# CircuitDesign.net
KiCad netlist of a schematic drawn in Altium Designer
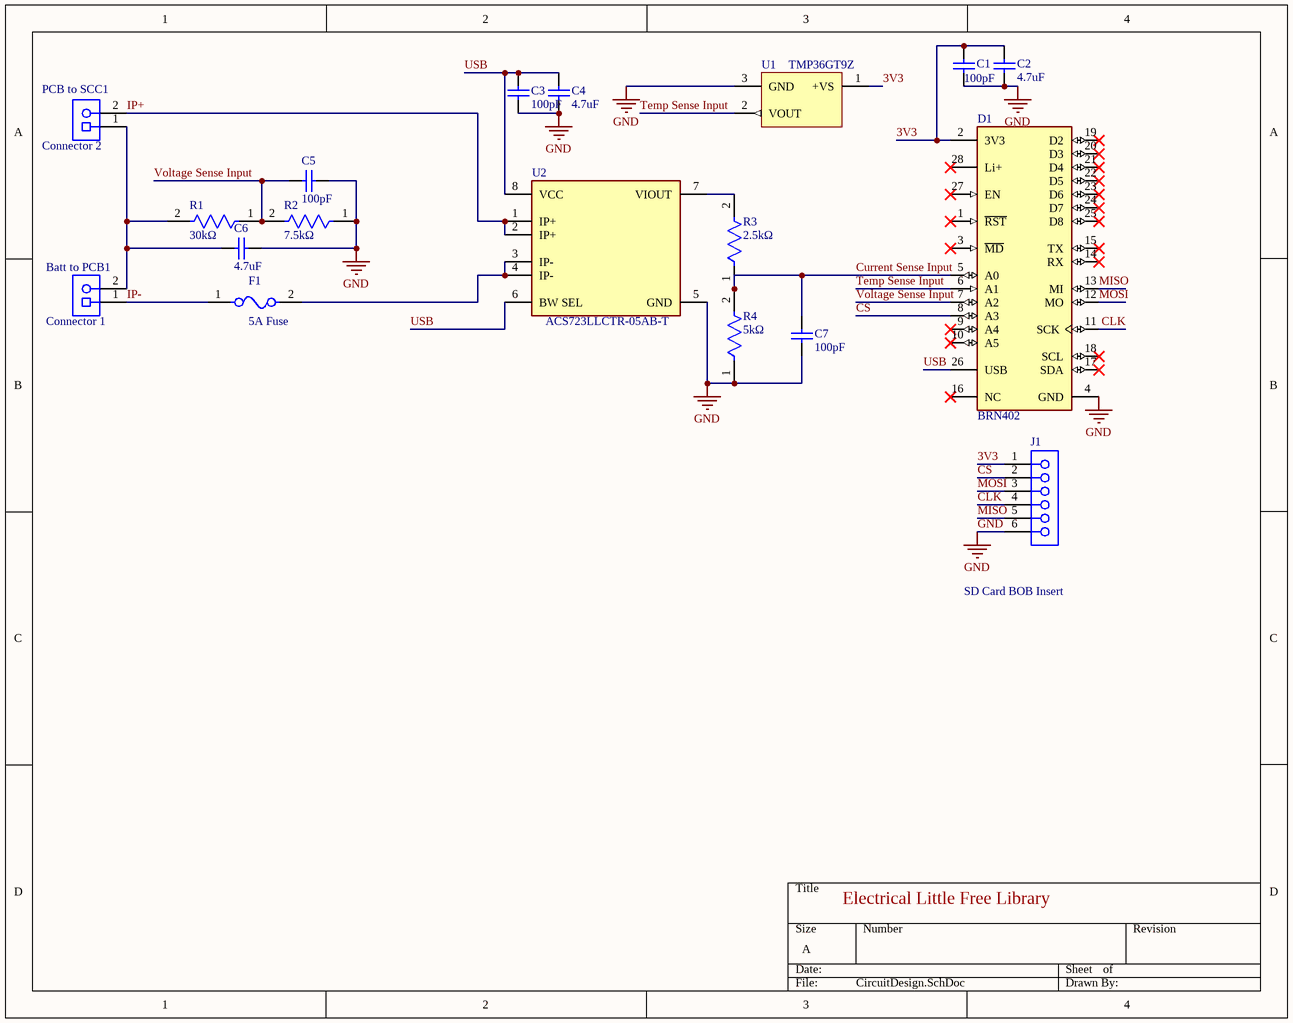
[diagram p0: CircuitDesign.SchDoc]

(export (version "E")
  (design (tool "Eeschema 10.0.6"))
  (components
    (comp (ref "Batt to PCB1")
      (value "Connector 1")
      (footprint "PHOE-1729128-2_V")
      (description "PCB Terminal Block, 13.5 A, 400 V, 2-Pin THD, RoHS, Bulk")
      (fields (field (name "PARTNUMBER") "1729128") (field (name "MANUFACTURER") "Phoenix Contact"))
      (libsource (lib "Altium Content Vault") (part "CN-2P-F-R2"))
    )
    (comp (ref "C1")
      (value "100pF")
      (footprint "CAPC1608X90X40ML10T20")
      (description "Chip Capacitor, 100 pF, +/- 5%, 50 V, -55 to 125 degC, 0603 (1608 Metric), RoHS, Tape and Reel")
      (fields (field (name "TOLERANCE") "5%") (field (name "VOLTAGE") "50V"))
      (libsource (lib "Altium Content Vault") (part "CAP-NP-2"))
    )
    (comp (ref "C2")
      (value "4.7uF")
      (footprint "CAPC2013X135X45LL10T25")
      (description "Chip Capacitor, 4.7 uF, +/- 10%, 16 V, -55 to 85 degC, 0805 (2012 Metric), RoHS, Tape and Reel")
      (fields (field (name "TOLERANCE") "10%") (field (name "PARTNUMBER") "GRM21BR61C475KA88L"))
      (libsource (lib "Altium Content Vault") (part "CAP-NP-2"))
    )
    (comp (ref "C3")
      (value "100pF")
      (footprint "CAPC1608X90X40ML10T20")
      (description "Chip Capacitor, 100 pF, +/- 5%, 50 V, -55 to 125 degC, 0603 (1608 Metric), RoHS, Tape and Reel")
      (fields (field (name "TOLERANCE") "5%") (field (name "VOLTAGE") "50V"))
      (libsource (lib "Altium Content Vault") (part "CAP-NP-2"))
    )
    (comp (ref "C4")
      (value "4.7uF")
      (footprint "CAPC2013X135X45LL10T25")
      (description "Chip Capacitor, 4.7 uF, +/- 10%, 16 V, -55 to 85 degC, 0805 (2012 Metric), RoHS, Tape and Reel")
      (fields (field (name "TOLERANCE") "10%") (field (name "PARTNUMBER") "GRM21BR61C475KA88L"))
      (libsource (lib "Altium Content Vault") (part "CAP-NP-2"))
    )
    (comp (ref "C5")
      (value "100pF")
      (footprint "CAPC1608X90X40ML10T20")
      (description "Chip Capacitor, 100 pF, +/- 5%, 50 V, -55 to 125 degC, 0603 (1608 Metric), RoHS, Tape and Reel")
      (fields (field (name "TOLERANCE") "5%") (field (name "VOLTAGE") "50V"))
      (libsource (lib "Altium Content Vault") (part "CAP-NP-2"))
    )
    (comp (ref "C6")
      (value "4.7uF")
      (footprint "CAPC2013X135X45LL10T25")
      (description "Chip Capacitor, 4.7 uF, +/- 10%, 16 V, -55 to 85 degC, 0805 (2012 Metric), RoHS, Tape and Reel")
      (fields (field (name "TOLERANCE") "10%") (field (name "PARTNUMBER") "GRM21BR61C475KA88L"))
      (libsource (lib "Altium Content Vault") (part "CAP-NP-2"))
    )
    (comp (ref "C7")
      (value "100pF")
      (footprint "CAPC1608X90X40ML10T20")
      (description "Chip Capacitor, 100 pF, +/- 5%, 50 V, -55 to 125 degC, 0603 (1608 Metric), RoHS, Tape and Reel")
      (fields (field (name "TOLERANCE") "5%") (field (name "VOLTAGE") "50V"))
      (libsource (lib "Altium Content Vault") (part "CAP-NP-2"))
    )
    (comp (ref "D1")
      (value "BRN402")
      (footprint "FP-BRN402-0")
      (description "BORON LTE")
      (fields
        (field (name "MANUFACTURER") "Particle")
        (field (name "OCTOPART") "https://octopart.com/brn402-particle-96116406")
      )
      (libsource (lib "Altium Content Vault") (part "69875060e2d83e17e1308076102c484"))
    )
    (comp (ref "F1")
      (value "5A Fuse")
      (footprint "FP-3568-MFG")
      (fields (field (name "VOLTAGE") "500V"))
      (libsource (lib "Altium Content Vault") (part "3568"))
    )
    (comp (ref "J1")
      (value "SD Card BOB Insert")
      (footprint "61300611821")
      (libsource (lib "Altium Content Vault") (part "Header_Female_1R_06P"))
    )
    (comp (ref "PCB to SCC1")
      (value "Connector 2")
      (footprint "PHOE-1729128-2_V")
      (description "PCB Terminal Block, 13.5 A, 400 V, 2-Pin THD, RoHS, Bulk")
      (fields (field (name "PARTNUMBER") "1729128") (field (name "MANUFACTURER") "Phoenix Contact"))
      (libsource (lib "Altium Content Vault") (part "CN-2P-F-R2"))
    )
    (comp (ref "R1")
      (value "30kΩ")
      (footprint "FP-CRCW0805-e3-MFG")
      (description "RES Thick Film, 30kΩ, 1%, 0.125W, 100ppm/°C, 0805")
      (fields (field (name "TOLERANCE") "1%"))
      (libsource (lib "Altium Content Vault") (part "1029c3af85768c4190bb7ad29bc67b5"))
    )
    (comp (ref "R2")
      (value "7.5kΩ")
      (footprint "FP-CR0805-IPC_B")
      (description "Thick Film Chip Resistors 0805 7.5kΩ 0.125W 1% 100ppm/°C")
      (fields (field (name "TOLERANCE") "1%"))
      (libsource (lib "Altium Content Vault") (part "1029c3af85768c4190bb7ad29bc67b5"))
    )
    (comp (ref "R3")
      (value "2.5kΩ")
      (footprint "FP-RN732A-IPC_B")
      (description "2.5kΩ ±0.1% 0.1W, 1/10W Chip Resistor 0805 (2012 Metric) Moisture Resistant Thin Film")
      (fields (field (name "TOLERANCE") "0.1%"))
      (libsource (lib "Altium Content Vault") (part "1029c3af85768c4190bb7ad29bc67b5"))
    )
    (comp (ref "R4")
      (value "5kΩ")
      (footprint "FP-RC0402-MFG")
      (description "RES SMD 5K OHM 1% 1/16W 0402")
      (fields (field (name "MANUFACTURER") "Yageo") (field (name "TOLERANCE") "1%"))
      (libsource (lib "Altium Content Vault") (part "1029c3af85768c4190bb7ad29bc67b5"))
    )
    (comp (ref "U1")
      (value "TMP36GT9Z")
      (footprint "ADI-T-3")
      (description "Low Voltage Temperature Sensor, 2.7 to 5.5 V Supply, Industrial, 3-pin TO92 (T-3), Tray")
      (fields (field (name "MANUFACTURER") "Analog Devices"))
      (libsource (lib "Altium Content Vault") (part "ADI-TMP3X-T-3"))
    )
    (comp (ref "U2")
      (value "ACS723LLCTR-05AB-T")
      (footprint "FP-LC-8-MFG")
      (description "SENSOR CURRENT HALL 5A AC/DC")
      (libsource (lib "Altium Content Vault") (part "4642a72edef107190d9bc917cb5a18f"))
    )
  )
  (nets
    (net (code "1") (name "/3V3") (class "Default")
      (node (ref "C1") (pin "1") (pinfunction "1_1") (pintype "passive"))
      (node (ref "C2") (pin "2") (pinfunction "2_2") (pintype "passive"))
      (node (ref "D1") (pin "2") (pinfunction "3V3_2") (pintype "power_in"))
      (node (ref "J1") (pin "1") (pinfunction "1_1") (pintype "passive"))
      (node (ref "U1") (pin "1") (pinfunction "+VS_1") (pintype "power_in"))
    )
    (net (code "3") (name "/CLK") (class "Default")
      (node (ref "D1") (pin "11") (pinfunction "SCK_11") (pintype "bidirectional"))
      (node (ref "J1") (pin "4") (pinfunction "4_4") (pintype "passive"))
    )
    (net (code "4") (name "/CS") (class "Default")
      (node (ref "D1") (pin "8") (pinfunction "A3_8") (pintype "bidirectional"))
      (node (ref "J1") (pin "2") (pinfunction "2_2") (pintype "passive"))
    )
    (net (code "5") (name "/Current Sense Input") (class "Default")
      (node (ref "C7") (pin "1") (pinfunction "1_1") (pintype "passive"))
      (node (ref "D1") (pin "5") (pinfunction "A0_5") (pintype "bidirectional"))
      (node (ref "R3") (pin "1") (pinfunction "1_1") (pintype "passive"))
      (node (ref "R4") (pin "2") (pinfunction "2_2") (pintype "passive"))
    )
    (net (code "6") (name "/IP+") (class "Default")
      (node (ref "PCB to SCC1") (pin "2") (pinfunction "2_2") (pintype "passive"))
      (node (ref "U2") (pin "1") (pinfunction "IP+_1") (pintype "passive"))
      (node (ref "U2") (pin "2") (pinfunction "IP+_2") (pintype "passive"))
    )
    (net (code "7") (name "/IP-") (class "Default")
      (node (ref "Batt to PCB1") (pin "1") (pinfunction "1_1") (pintype "passive"))
      (node (ref "F1") (pin "1") (pinfunction "1_1") (pintype "passive"))
    )
    (net (code "8") (name "/MISO") (class "Default")
      (node (ref "D1") (pin "13") (pinfunction "MI_13") (pintype "bidirectional"))
      (node (ref "J1") (pin "5") (pinfunction "5_5") (pintype "passive"))
    )
    (net (code "9") (name "/MOSI") (class "Default")
      (node (ref "D1") (pin "12") (pinfunction "MO_12") (pintype "bidirectional"))
      (node (ref "J1") (pin "3") (pinfunction "3_3") (pintype "passive"))
    )
    (net (code "10") (name "/Temp Sense Input") (class "Default")
      (node (ref "D1") (pin "6") (pinfunction "A1_6") (pintype "input"))
      (node (ref "U1") (pin "2") (pinfunction "VOUT_2") (pintype "output"))
    )
    (net (code "11") (name "/USB") (class "Default")
      (node (ref "C3") (pin "1") (pinfunction "1_1") (pintype "passive"))
      (node (ref "C4") (pin "2") (pinfunction "2_2") (pintype "passive"))
      (node (ref "D1") (pin "26") (pinfunction "USB_26") (pintype "passive"))
      (node (ref "U2") (pin "6") (pinfunction "BW_SEL_6") (pintype "passive"))
      (node (ref "U2") (pin "8") (pinfunction "VCC_8") (pintype "power_in"))
    )
    (net (code "12") (name "/Voltage Sense Input") (class "Default")
      (node (ref "C5") (pin "1") (pinfunction "1_1") (pintype "passive"))
      (node (ref "D1") (pin "7") (pinfunction "A2_7") (pintype "bidirectional"))
      (node (ref "R1") (pin "1") (pinfunction "1_1") (pintype "passive"))
      (node (ref "R2") (pin "2") (pinfunction "2_2") (pintype "passive"))
    )
    (net (code "13") (name "GND") (class "Default")
      (node (ref "C1") (pin "2") (pinfunction "2_2") (pintype "passive"))
      (node (ref "C2") (pin "1") (pinfunction "1_1") (pintype "passive"))
      (node (ref "C3") (pin "2") (pinfunction "2_2") (pintype "passive"))
      (node (ref "C4") (pin "1") (pinfunction "1_1") (pintype "passive"))
      (node (ref "C5") (pin "2") (pinfunction "2_2") (pintype "passive"))
      (node (ref "C6") (pin "1") (pinfunction "1_1") (pintype "passive"))
      (node (ref "C7") (pin "2") (pinfunction "2_2") (pintype "passive"))
      (node (ref "D1") (pin "4") (pinfunction "GND_4") (pintype "power_in"))
      (node (ref "J1") (pin "6") (pinfunction "6_6") (pintype "passive"))
      (node (ref "R2") (pin "1") (pinfunction "1_1") (pintype "passive"))
      (node (ref "R4") (pin "1") (pinfunction "1_1") (pintype "passive"))
      (node (ref "U1") (pin "3") (pinfunction "GND_3") (pintype "power_in"))
      (node (ref "U2") (pin "5") (pinfunction "GND_5") (pintype "power_in"))
    )
    (net (code "14") (name "Net-(Batt to PCB1-Pad2)") (class "Default")
      (node (ref "Batt to PCB1") (pin "2") (pinfunction "2_2") (pintype "passive"))
      (node (ref "C6") (pin "2") (pinfunction "2_2") (pintype "passive"))
      (node (ref "PCB to SCC1") (pin "1") (pinfunction "1_1") (pintype "passive"))
      (node (ref "R1") (pin "2") (pinfunction "2_2") (pintype "passive"))
    )
    (net (code "15") (name "Net-(F1-Pad2)") (class "Default")
      (node (ref "F1") (pin "2") (pinfunction "2_2") (pintype "passive"))
      (node (ref "U2") (pin "3") (pinfunction "IP-_3") (pintype "passive"))
      (node (ref "U2") (pin "4") (pinfunction "IP-_4") (pintype "passive"))
    )
    (net (code "16") (name "Net-(U2-VIOUT)") (class "Default")
      (node (ref "R3") (pin "2") (pinfunction "2_2") (pintype "passive"))
      (node (ref "U2") (pin "7") (pinfunction "VIOUT_7") (pintype "passive"))
    )
    (net (code "17") (name "unconnected-(D1-A4-Pad9)") (class "Default")
      (node (ref "D1") (pin "9") (pinfunction "A4_9") (pintype "bidirectional+no_connect"))
    )
    (net (code "18") (name "unconnected-(D1-A5-Pad10)") (class "Default")
      (node (ref "D1") (pin "10") (pinfunction "A5_10") (pintype "bidirectional+no_connect"))
    )
    (net (code "19") (name "unconnected-(D1-D2-Pad19)") (class "Default")
      (node (ref "D1") (pin "19") (pinfunction "D2_19") (pintype "bidirectional+no_connect"))
    )
    (net (code "20") (name "unconnected-(D1-D3-Pad20)") (class "Default")
      (node (ref "D1") (pin "20") (pinfunction "D3_20") (pintype "bidirectional+no_connect"))
    )
    (net (code "21") (name "unconnected-(D1-D4-Pad21)") (class "Default")
      (node (ref "D1") (pin "21") (pinfunction "D4_21") (pintype "bidirectional+no_connect"))
    )
    (net (code "22") (name "unconnected-(D1-D5-Pad22)") (class "Default")
      (node (ref "D1") (pin "22") (pinfunction "D5_22") (pintype "bidirectional+no_connect"))
    )
    (net (code "23") (name "unconnected-(D1-D6-Pad23)") (class "Default")
      (node (ref "D1") (pin "23") (pinfunction "D6_23") (pintype "bidirectional+no_connect"))
    )
    (net (code "24") (name "unconnected-(D1-D7-Pad24)") (class "Default")
      (node (ref "D1") (pin "24") (pinfunction "D7_24") (pintype "bidirectional+no_connect"))
    )
    (net (code "25") (name "unconnected-(D1-D8-Pad25)") (class "Default")
      (node (ref "D1") (pin "25") (pinfunction "D8_25") (pintype "bidirectional+no_connect"))
    )
    (net (code "26") (name "unconnected-(D1-EN-Pad27)") (class "Default")
      (node (ref "D1") (pin "27") (pinfunction "EN_27") (pintype "input+no_connect"))
    )
    (net (code "27") (name "unconnected-(D1-Li+-Pad28)") (class "Default")
      (node (ref "D1") (pin "28") (pinfunction "Li+_28") (pintype "power_in+no_connect"))
    )
    (net (code "28") (name "unconnected-(D1-NC-Pad16)") (class "Default")
      (node (ref "D1") (pin "16") (pinfunction "NC_16") (pintype "passive+no_connect"))
    )
    (net (code "29") (name "unconnected-(D1-RX-Pad14)") (class "Default")
      (node (ref "D1") (pin "14") (pinfunction "RX_14") (pintype "bidirectional+no_connect"))
    )
    (net (code "30") (name "unconnected-(D1-SCL-Pad18)") (class "Default")
      (node (ref "D1") (pin "18") (pinfunction "SCL_18") (pintype "bidirectional+no_connect"))
    )
    (net (code "31") (name "unconnected-(D1-SDA-Pad17)") (class "Default")
      (node (ref "D1") (pin "17") (pinfunction "SDA_17") (pintype "bidirectional+no_connect"))
    )
    (net (code "32") (name "unconnected-(D1-TX-Pad15)") (class "Default")
      (node (ref "D1") (pin "15") (pinfunction "TX_15") (pintype "bidirectional+no_connect"))
    )
    (net (code "33") (name "unconnected-(D1-~{MD}-Pad3)") (class "Default")
      (node (ref "D1") (pin "3") (pinfunction "~{MD}_3") (pintype "input+no_connect"))
    )
    (net (code "34") (name "unconnected-(D1-~{RST}-Pad1)") (class "Default")
      (node (ref "D1") (pin "1") (pinfunction "~{RST}_1") (pintype "input+no_connect"))
    )
  )
)
